# LED.net
KiCad netlist of a schematic drawn in Altium Designer
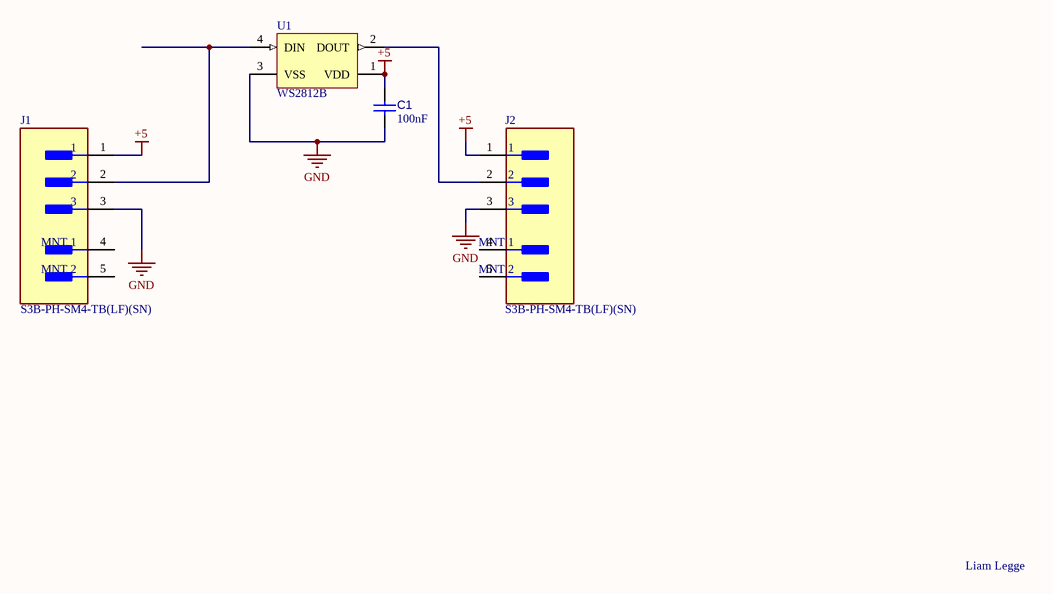
[diagram p0: LED.SchDoc]

(export (version "E")
  (design (tool "Eeschema 10.0.6"))
  (components
    (comp (ref "C1")
      (value "100nF")
      (footprint "3")
      (description "CAP CER 100 nF 50V X7R 0603")
      (fields (field (name "TOLERANCE") "10%") (field (name "LCSC PART NUMBER") "C14663"))
      (libsource (lib "Dalhousie Formula SAE") (part "CAP-NP-2"))
    )
    (comp (ref "J1")
      (value "S3B-PH-SM4-TB(LF)(SN)")
      (footprint "FP-S3B-PH-SM4-TB_LF_SN-MFG")
      (description "CONN HEADER SMD R/A 3POS 2MM")
      (libsource (lib "Altium Content Vault") (part "38689d6f3df0f9b234c6ddcef280d85"))
    )
    (comp (ref "J2")
      (value "S3B-PH-SM4-TB(LF)(SN)")
      (footprint "FP-S3B-PH-SM4-TB_LF_SN-MFG")
      (description "CONN HEADER SMD R/A 3POS 2MM")
      (libsource (lib "") (part "38689d6f3df0f9b234c6ddcef280d85_1"))
    )
    (comp (ref "U1")
      (value "WS2812B")
      (footprint "ADAI-WS2812B_V")
      (fields (field (name "MANUFACTURER") "Adafruit Industries"))
      (libsource (lib "Dalhousie Formula SAE") (part "ADAI-WS2812B-4"))
    )
  )
  (nets
    (net (code "1") (name "+5") (class "Default")
      (node (ref "C1") (pin "2") (pinfunction "2_2") (pintype "passive"))
      (node (ref "J1") (pin "1") (pinfunction "1_1") (pintype "passive"))
      (node (ref "J2") (pin "1") (pinfunction "1_1") (pintype "passive"))
      (node (ref "U1") (pin "1") (pinfunction "VDD_1") (pintype "power_in"))
    )
    (net (code "2") (name "GND") (class "Default")
      (node (ref "C1") (pin "1") (pinfunction "1_1") (pintype "passive"))
      (node (ref "J1") (pin "3") (pinfunction "3_3") (pintype "passive"))
      (node (ref "J2") (pin "3") (pinfunction "3_3") (pintype "passive"))
      (node (ref "U1") (pin "3") (pinfunction "VSS_3") (pintype "power_in"))
    )
    (net (code "3") (name "Net-(U1-DIN)") (class "Default")
      (node (ref "J1") (pin "2") (pinfunction "2_2") (pintype "passive"))
      (node (ref "U1") (pin "4") (pinfunction "DIN_4") (pintype "input"))
    )
    (net (code "4") (name "Net-(U1-DOUT)") (class "Default")
      (node (ref "J2") (pin "2") (pinfunction "2_2") (pintype "passive"))
      (node (ref "U1") (pin "2") (pinfunction "DOUT_2") (pintype "output"))
    )
    (net (code "5") (name "unconnected-(J1-MNT_1-Pad4)") (class "Default")
      (node (ref "J1") (pin "4") (pinfunction "MNT_1_4") (pintype "passive"))
    )
    (net (code "6") (name "unconnected-(J1-MNT_2-Pad5)") (class "Default")
      (node (ref "J1") (pin "5") (pinfunction "MNT_2_5") (pintype "passive"))
    )
    (net (code "7") (name "unconnected-(J2-MNT_1-Pad4)") (class "Default")
      (node (ref "J2") (pin "4") (pinfunction "MNT_1_4") (pintype "passive"))
    )
    (net (code "8") (name "unconnected-(J2-MNT_2-Pad5)") (class "Default")
      (node (ref "J2") (pin "5") (pinfunction "MNT_2_5") (pintype "passive"))
    )
  )
)
